# Main.net
KiCad netlist of a schematic drawn in EAGLE
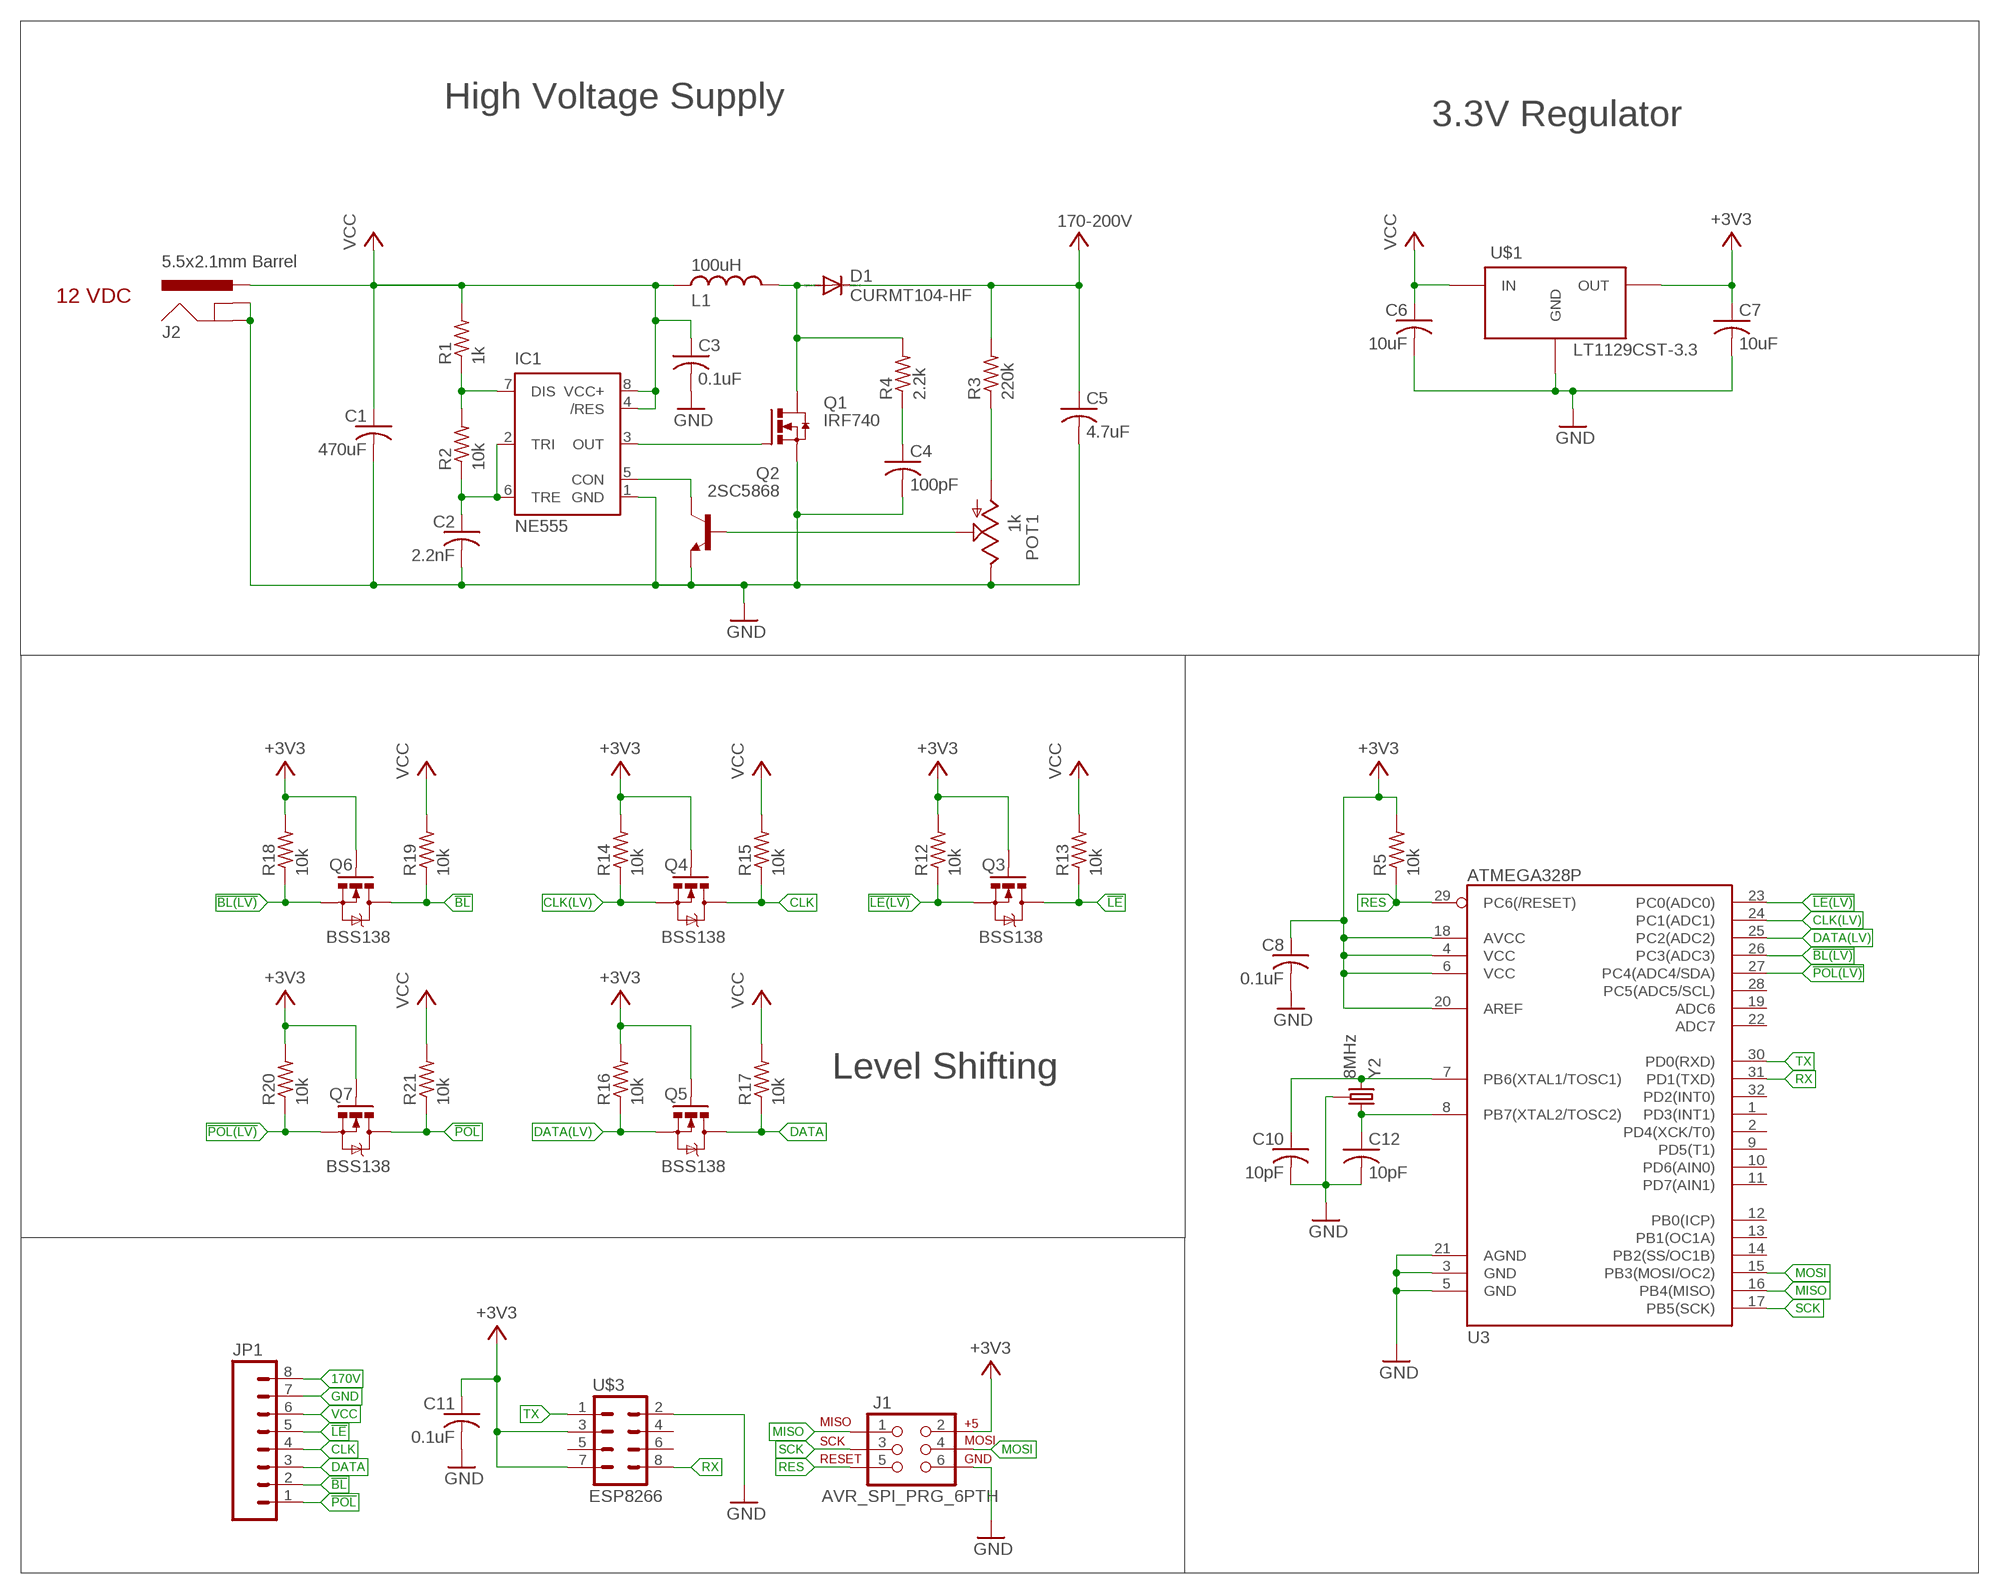
[diagram p0: schematic, sheet 1]

(export (version "E")
  (design (tool "Eeschema 10.0.6"))
  (components
    (comp (ref "C1")
      (value "470uF")
      (footprint "eagle-import:C0603")
      (libsource (lib "eagle-import") (part "C-USC0603"))
    )
    (comp (ref "C2")
      (value "2.2nF")
      (footprint "eagle-import:C0603")
      (libsource (lib "eagle-import") (part "C-USC0603"))
    )
    (comp (ref "C3")
      (value "0.1uF")
      (footprint "eagle-import:C0603")
      (libsource (lib "eagle-import") (part "C-USC0603"))
    )
    (comp (ref "C4")
      (value "100pF")
      (footprint "eagle-import:C0603")
      (libsource (lib "eagle-import") (part "C-USC0603"))
    )
    (comp (ref "C5")
      (value "4.7uF")
      (footprint "eagle-import:C0603")
      (libsource (lib "eagle-import") (part "C-USC0603"))
    )
    (comp (ref "C6")
      (value "10uF")
      (footprint "eagle-import:C0603")
      (libsource (lib "eagle-import") (part "C-USC0603"))
    )
    (comp (ref "C7")
      (value "10uF")
      (footprint "eagle-import:C0603")
      (libsource (lib "eagle-import") (part "C-USC0603"))
    )
    (comp (ref "C8")
      (value "0.1uF")
      (footprint "eagle-import:C0603")
      (libsource (lib "eagle-import") (part "C-USC0603"))
    )
    (comp (ref "C10")
      (value "10pF")
      (footprint "eagle-import:C0603")
      (libsource (lib "eagle-import") (part "C-USC0603"))
    )
    (comp (ref "C11")
      (value "0.1uF")
      (footprint "eagle-import:C0603")
      (libsource (lib "eagle-import") (part "C-USC0603"))
    )
    (comp (ref "C12")
      (value "10pF")
      (footprint "eagle-import:C0603")
      (libsource (lib "eagle-import") (part "C-USC0603"))
    )
    (comp (ref "D1")
      (value "CURMT104-HF")
      (footprint "eagle-import:SOD-123_MINI-SMA")
      (libsource (lib "eagle-import") (part "CGRM400-G1"))
    )
    (comp (ref "IC1")
      (value "NE555")
      (footprint "eagle-import:SO08")
      (libsource (lib "eagle-import") (part "NE555D"))
    )
    (comp (ref "J1")
      (value "AVR_SPI_PRG_6PTH")
      (footprint "eagle-import:2X3")
      (libsource (lib "eagle-import") (part "AVR_SPI_PRG_6PTH"))
    )
    (comp (ref "J2")
      (value "5.5x2.1mm Barrel")
      (footprint "eagle-import:POWER_JACK_SMD")
      (libsource (lib "eagle-import") (part "POWER_JACKSMD"))
    )
    (comp (ref "JP1")
      (value "M08")
      (footprint "eagle-import:1X08_PIN1_NO_SILK")
      (libsource (lib "eagle-import") (part "M08"))
    )
    (comp (ref "L1")
      (value "100uH")
      (footprint "eagle-import:L2012C")
      (libsource (lib "eagle-import") (part "L-USL2012C"))
    )
    (comp (ref "POT1")
      (value "1k")
      (footprint "eagle-import:1X03")
      (libsource (lib "eagle-import") (part "TRIM_US-DIL3"))
    )
    (comp (ref "Q1")
      (value "IRF740")
      (footprint "eagle-import:D2PACK")
      (libsource (lib "eagle-import") (part "IRF3704S"))
    )
    (comp (ref "Q2")
      (value "2SC5868")
      (footprint "eagle-import:SOT23-BEC")
      (libsource (lib "eagle-import") (part "BC850SMD"))
    )
    (comp (ref "Q3")
      (value "BSS138")
      (footprint "eagle-import:SOT23")
      (libsource (lib "eagle-import") (part "MOSFET-NCHANNELBSS138"))
    )
    (comp (ref "Q4")
      (value "BSS138")
      (footprint "eagle-import:SOT23")
      (libsource (lib "eagle-import") (part "MOSFET-NCHANNELBSS138"))
    )
    (comp (ref "Q5")
      (value "BSS138")
      (footprint "eagle-import:SOT23")
      (libsource (lib "eagle-import") (part "MOSFET-NCHANNELBSS138"))
    )
    (comp (ref "Q6")
      (value "BSS138")
      (footprint "eagle-import:SOT23")
      (libsource (lib "eagle-import") (part "MOSFET-NCHANNELBSS138"))
    )
    (comp (ref "Q7")
      (value "BSS138")
      (footprint "eagle-import:SOT23")
      (libsource (lib "eagle-import") (part "MOSFET-NCHANNELBSS138"))
    )
    (comp (ref "R1")
      (value "1k")
      (footprint "eagle-import:R0603")
      (libsource (lib "eagle-import") (part "R-US_R0603"))
    )
    (comp (ref "R2")
      (value "10k")
      (footprint "eagle-import:R0603")
      (libsource (lib "eagle-import") (part "R-US_R0603"))
    )
    (comp (ref "R3")
      (value "220k")
      (footprint "eagle-import:R0603")
      (libsource (lib "eagle-import") (part "R-US_R0603"))
    )
    (comp (ref "R4")
      (value "2.2k")
      (footprint "eagle-import:R0603")
      (libsource (lib "eagle-import") (part "R-US_R0603"))
    )
    (comp (ref "R5")
      (value "10k")
      (footprint "eagle-import:R0603")
      (libsource (lib "eagle-import") (part "R-US_R0603"))
    )
    (comp (ref "R12")
      (value "10k")
      (footprint "eagle-import:R0603")
      (libsource (lib "eagle-import") (part "R-US_R0603"))
    )
    (comp (ref "R13")
      (value "10k")
      (footprint "eagle-import:R0603")
      (libsource (lib "eagle-import") (part "R-US_R0603"))
    )
    (comp (ref "R14")
      (value "10k")
      (footprint "eagle-import:R0603")
      (libsource (lib "eagle-import") (part "R-US_R0603"))
    )
    (comp (ref "R15")
      (value "10k")
      (footprint "eagle-import:R0603")
      (libsource (lib "eagle-import") (part "R-US_R0603"))
    )
    (comp (ref "R16")
      (value "10k")
      (footprint "eagle-import:R0603")
      (libsource (lib "eagle-import") (part "R-US_R0603"))
    )
    (comp (ref "R17")
      (value "10k")
      (footprint "eagle-import:R0603")
      (libsource (lib "eagle-import") (part "R-US_R0603"))
    )
    (comp (ref "R18")
      (value "10k")
      (footprint "eagle-import:R0603")
      (libsource (lib "eagle-import") (part "R-US_R0603"))
    )
    (comp (ref "R19")
      (value "10k")
      (footprint "eagle-import:R0603")
      (libsource (lib "eagle-import") (part "R-US_R0603"))
    )
    (comp (ref "R20")
      (value "10k")
      (footprint "eagle-import:R0603")
      (libsource (lib "eagle-import") (part "R-US_R0603"))
    )
    (comp (ref "R21")
      (value "10k")
      (footprint "eagle-import:R0603")
      (libsource (lib "eagle-import") (part "R-US_R0603"))
    )
    (comp (ref "U$1")
      (value "LT1129CST-3.3")
      (footprint "eagle-import:SOT-223")
      (libsource (lib "eagle-import") (part "LT1129CST-3.3"))
    )
    (comp (ref "U$3")
      (value "ESP8266")
      (footprint "eagle-import:2X4")
      (libsource (lib "eagle-import") (part "M04X2"))
    )
    (comp (ref "U3")
      (value "ATMEGA328P")
      (footprint "eagle-import:TQFP32-08")
      (libsource (lib "eagle-import") (part "ATMEGA328_SMT"))
    )
    (comp (ref "Y2")
      (value "8MHz")
      (footprint "eagle-import:CTS406")
      (libsource (lib "eagle-import") (part "CRYSTALCTS406"))
    )
  )
  (nets
    (net (code "1") (name "+3V3") (class "Default")
      (node (ref "C11") (pin "1") (pinfunction "1_1") (pintype "passive"))
      (node (ref "C7") (pin "1") (pinfunction "1_1") (pintype "passive"))
      (node (ref "C8") (pin "1") (pinfunction "1_1") (pintype "passive"))
      (node (ref "J1") (pin "2") (pinfunction "2_2") (pintype "passive"))
      (node (ref "Q3") (pin "1") (pinfunction "G_1") (pintype "passive"))
      (node (ref "Q4") (pin "1") (pinfunction "G_1") (pintype "passive"))
      (node (ref "Q5") (pin "1") (pinfunction "G_1") (pintype "passive"))
      (node (ref "Q6") (pin "1") (pinfunction "G_1") (pintype "passive"))
      (node (ref "Q7") (pin "1") (pinfunction "G_1") (pintype "passive"))
      (node (ref "R12") (pin "2") (pinfunction "2_2") (pintype "passive"))
      (node (ref "R14") (pin "2") (pinfunction "2_2") (pintype "passive"))
      (node (ref "R16") (pin "2") (pinfunction "2_2") (pintype "passive"))
      (node (ref "R18") (pin "2") (pinfunction "2_2") (pintype "passive"))
      (node (ref "R20") (pin "2") (pinfunction "2_2") (pintype "passive"))
      (node (ref "R5") (pin "2") (pinfunction "2_2") (pintype "passive"))
      (node (ref "U$1") (pin "VOUT") (pinfunction "OUT_VOUT") (pintype "power_in"))
      (node (ref "U$3") (pin "3") (pinfunction "3_3") (pintype "passive"))
      (node (ref "U$3") (pin "7") (pinfunction "7_7") (pintype "passive"))
      (node (ref "U3") (pin "18") (pinfunction "AVCC_18") (pintype "bidirectional"))
      (node (ref "U3") (pin "20") (pinfunction "AREF_20") (pintype "bidirectional"))
      (node (ref "U3") (pin "4") (pinfunction "VCC_4") (pintype "bidirectional"))
      (node (ref "U3") (pin "6") (pinfunction "VCC_6") (pintype "bidirectional"))
    )
    (net (code "2") (name "/~{BL(LV})") (class "Default")
      (node (ref "Q6") (pin "2") (pinfunction "S_2") (pintype "passive"))
      (node (ref "R18") (pin "1") (pinfunction "1_1") (pintype "passive"))
      (node (ref "U3") (pin "26") (pinfunction "PC3(ADC3)_26") (pintype "bidirectional"))
    )
    (net (code "3") (name "/~{BL}") (class "Default")
      (node (ref "JP1") (pin "2") (pinfunction "2_2") (pintype "passive"))
      (node (ref "Q6") (pin "3") (pinfunction "D_3") (pintype "passive"))
      (node (ref "R19") (pin "1") (pinfunction "1_1") (pintype "passive"))
    )
    (net (code "4") (name "/~{LE(LV})") (class "Default")
      (node (ref "Q3") (pin "2") (pinfunction "S_2") (pintype "passive"))
      (node (ref "R12") (pin "1") (pinfunction "1_1") (pintype "passive"))
      (node (ref "U3") (pin "23") (pinfunction "PC0(ADC0)_23") (pintype "bidirectional"))
    )
    (net (code "5") (name "/~{LE}") (class "Default")
      (node (ref "JP1") (pin "5") (pinfunction "5_5") (pintype "passive"))
      (node (ref "Q3") (pin "3") (pinfunction "D_3") (pintype "passive"))
      (node (ref "R13") (pin "1") (pinfunction "1_1") (pintype "passive"))
    )
    (net (code "6") (name "/~{POL(LV})") (class "Default")
      (node (ref "Q7") (pin "2") (pinfunction "S_2") (pintype "passive"))
      (node (ref "R20") (pin "1") (pinfunction "1_1") (pintype "passive"))
      (node (ref "U3") (pin "27") (pinfunction "PC4(ADC4/SDA)_27") (pintype "bidirectional"))
    )
    (net (code "7") (name "/~{POL}") (class "Default")
      (node (ref "JP1") (pin "1") (pinfunction "1_1") (pintype "passive"))
      (node (ref "Q7") (pin "3") (pinfunction "D_3") (pintype "passive"))
      (node (ref "R21") (pin "1") (pinfunction "1_1") (pintype "passive"))
    )
    (net (code "8") (name "170V") (class "Default")
      (node (ref "C5") (pin "1") (pinfunction "1_1") (pintype "passive"))
      (node (ref "D1") (pin "C") (pinfunction "C_C") (pintype "passive"))
      (node (ref "JP1") (pin "8") (pinfunction "8_8") (pintype "passive"))
      (node (ref "R3") (pin "2") (pinfunction "2_2") (pintype "passive"))
    )
    (net (code "9") (name "CLK") (class "Default")
      (node (ref "JP1") (pin "4") (pinfunction "4_4") (pintype "passive"))
      (node (ref "Q4") (pin "3") (pinfunction "D_3") (pintype "passive"))
      (node (ref "R15") (pin "1") (pinfunction "1_1") (pintype "passive"))
    )
    (net (code "10") (name "CLK(LV)") (class "Default")
      (node (ref "Q4") (pin "2") (pinfunction "S_2") (pintype "passive"))
      (node (ref "R14") (pin "1") (pinfunction "1_1") (pintype "passive"))
      (node (ref "U3") (pin "24") (pinfunction "PC1(ADC1)_24") (pintype "bidirectional"))
    )
    (net (code "11") (name "DATA") (class "Default")
      (node (ref "JP1") (pin "3") (pinfunction "3_3") (pintype "passive"))
      (node (ref "Q5") (pin "3") (pinfunction "D_3") (pintype "passive"))
      (node (ref "R17") (pin "1") (pinfunction "1_1") (pintype "passive"))
    )
    (net (code "12") (name "DATA(LV)") (class "Default")
      (node (ref "Q5") (pin "2") (pinfunction "S_2") (pintype "passive"))
      (node (ref "R16") (pin "1") (pinfunction "1_1") (pintype "passive"))
      (node (ref "U3") (pin "25") (pinfunction "PC2(ADC2)_25") (pintype "bidirectional"))
    )
    (net (code "13") (name "GND") (class "Default")
      (node (ref "C1") (pin "2") (pinfunction "2_2") (pintype "passive"))
      (node (ref "C10") (pin "2") (pinfunction "2_2") (pintype "passive"))
      (node (ref "C11") (pin "2") (pinfunction "2_2") (pintype "passive"))
      (node (ref "C12") (pin "2") (pinfunction "2_2") (pintype "passive"))
      (node (ref "C2") (pin "2") (pinfunction "2_2") (pintype "passive"))
      (node (ref "C3") (pin "2") (pinfunction "2_2") (pintype "passive"))
      (node (ref "C4") (pin "2") (pinfunction "2_2") (pintype "passive"))
      (node (ref "C5") (pin "2") (pinfunction "2_2") (pintype "passive"))
      (node (ref "C6") (pin "2") (pinfunction "2_2") (pintype "passive"))
      (node (ref "C7") (pin "2") (pinfunction "2_2") (pintype "passive"))
      (node (ref "C8") (pin "2") (pinfunction "2_2") (pintype "passive"))
      (node (ref "IC1") (pin "1") (pinfunction "GND_1") (pintype "power_in"))
      (node (ref "J1") (pin "6") (pinfunction "6_6") (pintype "passive"))
      (node (ref "J2") (pin "GND") (pinfunction "GNDBREAK_GND") (pintype "bidirectional"))
      (node (ref "J2") (pin "P$4") (pinfunction "GND_P$4") (pintype "bidirectional"))
      (node (ref "JP1") (pin "7") (pinfunction "7_7") (pintype "passive"))
      (node (ref "POT1") (pin "3") (pinfunction "E_3") (pintype "passive"))
      (node (ref "Q1") (pin "3") (pinfunction "S_3") (pintype "passive"))
      (node (ref "Q2") (pin "E") (pinfunction "E_E") (pintype "passive"))
      (node (ref "U$1") (pin "GND") (pinfunction "GND_GND") (pintype "power_in"))
      (node (ref "U$1") (pin "GND1") (pinfunction "GND_GND1") (pintype "power_in"))
      (node (ref "U$3") (pin "2") (pinfunction "2_2") (pintype "passive"))
      (node (ref "U3") (pin "21") (pinfunction "AGND_21") (pintype "bidirectional"))
      (node (ref "U3") (pin "3") (pinfunction "GND_3") (pintype "bidirectional"))
      (node (ref "U3") (pin "5") (pinfunction "GND_5") (pintype "bidirectional"))
      (node (ref "Y2") (pin "2") (pinfunction "GND_2") (pintype "passive"))
      (node (ref "Y2") (pin "4") (pinfunction "GND_4") (pintype "passive"))
    )
    (net (code "14") (name "MISO") (class "Default")
      (node (ref "J1") (pin "1") (pinfunction "1_1") (pintype "passive"))
      (node (ref "U3") (pin "16") (pinfunction "PB4(MISO)_16") (pintype "bidirectional"))
    )
    (net (code "15") (name "MOSI") (class "Default")
      (node (ref "J1") (pin "4") (pinfunction "4_4") (pintype "passive"))
      (node (ref "U3") (pin "15") (pinfunction "PB3(MOSI/OC2)_15") (pintype "bidirectional"))
    )
    (net (code "16") (name "Net-(C4-Pad1)") (class "Default")
      (node (ref "C4") (pin "1") (pinfunction "1_1") (pintype "passive"))
      (node (ref "R4") (pin "1") (pinfunction "1_1") (pintype "passive"))
    )
    (net (code "17") (name "Net-(IC1-CON)") (class "Default")
      (node (ref "IC1") (pin "5") (pinfunction "CON_5") (pintype "input"))
      (node (ref "Q2") (pin "C") (pinfunction "C_C") (pintype "passive"))
    )
    (net (code "18") (name "Net-(IC1-DIS)") (class "Default")
      (node (ref "IC1") (pin "7") (pinfunction "DIS_7") (pintype "input"))
      (node (ref "R1") (pin "1") (pinfunction "1_1") (pintype "passive"))
      (node (ref "R2") (pin "2") (pinfunction "2_2") (pintype "passive"))
    )
    (net (code "19") (name "Net-(IC1-OUT)") (class "Default")
      (node (ref "IC1") (pin "3") (pinfunction "OUT_3") (pintype "output"))
      (node (ref "Q1") (pin "1") (pinfunction "G_1") (pintype "passive"))
    )
    (net (code "20") (name "Net-(IC1-TRE)") (class "Default")
      (node (ref "C2") (pin "1") (pinfunction "1_1") (pintype "passive"))
      (node (ref "IC1") (pin "2") (pinfunction "TRI_2") (pintype "input"))
      (node (ref "IC1") (pin "6") (pinfunction "TRE_6") (pintype "input"))
      (node (ref "R2") (pin "1") (pinfunction "1_1") (pintype "passive"))
    )
    (net (code "21") (name "Net-(POT1-A)") (class "Default")
      (node (ref "POT1") (pin "1") (pinfunction "A_1") (pintype "passive"))
      (node (ref "R3") (pin "1") (pinfunction "1_1") (pintype "passive"))
    )
    (net (code "22") (name "Net-(POT1-S)") (class "Default")
      (node (ref "POT1") (pin "2") (pinfunction "S_2") (pintype "passive"))
      (node (ref "Q2") (pin "B") (pinfunction "B_B") (pintype "passive"))
    )
    (net (code "23") (name "Net-(Q1-D)") (class "Default")
      (node (ref "D1") (pin "A") (pinfunction "A_A") (pintype "passive"))
      (node (ref "L1") (pin "1") (pinfunction "1_1") (pintype "passive"))
      (node (ref "Q1") (pin "2") (pinfunction "D_2") (pintype "passive"))
      (node (ref "R4") (pin "2") (pinfunction "2_2") (pintype "passive"))
    )
    (net (code "24") (name "Net-(U3-PB6(XTAL1{slash}TOSC1))") (class "Default")
      (node (ref "C10") (pin "1") (pinfunction "1_1") (pintype "passive"))
      (node (ref "U3") (pin "7") (pinfunction "PB6(XTAL1/TOSC1)_7") (pintype "bidirectional"))
      (node (ref "Y2") (pin "3") (pinfunction "2_3") (pintype "passive"))
    )
    (net (code "25") (name "Net-(U3-PB7(XTAL2{slash}TOSC2))") (class "Default")
      (node (ref "C12") (pin "1") (pinfunction "1_1") (pintype "passive"))
      (node (ref "U3") (pin "8") (pinfunction "PB7(XTAL2/TOSC2)_8") (pintype "bidirectional"))
      (node (ref "Y2") (pin "1") (pinfunction "1_1") (pintype "passive"))
    )
    (net (code "26") (name "RES") (class "Default")
      (node (ref "J1") (pin "5") (pinfunction "5_5") (pintype "passive"))
      (node (ref "R5") (pin "1") (pinfunction "1_1") (pintype "passive"))
      (node (ref "U3") (pin "29") (pinfunction "PC6(/RESET)_29") (pintype "bidirectional"))
    )
    (net (code "27") (name "RX") (class "Default")
      (node (ref "U$3") (pin "8") (pinfunction "8_8") (pintype "passive"))
      (node (ref "U3") (pin "31") (pinfunction "PD1(TXD)_31") (pintype "bidirectional"))
    )
    (net (code "28") (name "SCK") (class "Default")
      (node (ref "J1") (pin "3") (pinfunction "3_3") (pintype "passive"))
      (node (ref "U3") (pin "17") (pinfunction "PB5(SCK)_17") (pintype "bidirectional"))
    )
    (net (code "29") (name "TX") (class "Default")
      (node (ref "U$3") (pin "1") (pinfunction "1_1") (pintype "passive"))
      (node (ref "U3") (pin "30") (pinfunction "PD0(RXD)_30") (pintype "bidirectional"))
    )
    (net (code "30") (name "VCC") (class "Default")
      (node (ref "C1") (pin "1") (pinfunction "1_1") (pintype "passive"))
      (node (ref "C3") (pin "1") (pinfunction "1_1") (pintype "passive"))
      (node (ref "C6") (pin "1") (pinfunction "1_1") (pintype "passive"))
      (node (ref "IC1") (pin "4") (pinfunction "/RES_4") (pintype "input"))
      (node (ref "IC1") (pin "8") (pinfunction "VCC+_8") (pintype "power_in"))
      (node (ref "J2") (pin "VIN0") (pinfunction "PWR_VIN0") (pintype "bidirectional"))
      (node (ref "JP1") (pin "6") (pinfunction "6_6") (pintype "passive"))
      (node (ref "L1") (pin "2") (pinfunction "2_2") (pintype "passive"))
      (node (ref "R1") (pin "2") (pinfunction "2_2") (pintype "passive"))
      (node (ref "R13") (pin "2") (pinfunction "2_2") (pintype "passive"))
      (node (ref "R15") (pin "2") (pinfunction "2_2") (pintype "passive"))
      (node (ref "R17") (pin "2") (pinfunction "2_2") (pintype "passive"))
      (node (ref "R19") (pin "2") (pinfunction "2_2") (pintype "passive"))
      (node (ref "R21") (pin "2") (pinfunction "2_2") (pintype "passive"))
      (node (ref "U$1") (pin "VIN") (pinfunction "IN_VIN") (pintype "power_in"))
    )
    (net (code "31") (name "unconnected-(U$3-Pad4)") (class "Default")
      (node (ref "U$3") (pin "4") (pinfunction "4_4") (pintype "passive"))
    )
    (net (code "32") (name "unconnected-(U$3-Pad5)") (class "Default")
      (node (ref "U$3") (pin "5") (pinfunction "5_5") (pintype "passive"))
    )
    (net (code "33") (name "unconnected-(U$3-Pad6)") (class "Default")
      (node (ref "U$3") (pin "6") (pinfunction "6_6") (pintype "passive"))
    )
    (net (code "34") (name "unconnected-(U3-ADC6-Pad19)") (class "Default")
      (node (ref "U3") (pin "19") (pinfunction "ADC6_19") (pintype "bidirectional"))
    )
    (net (code "35") (name "unconnected-(U3-ADC7-Pad22)") (class "Default")
      (node (ref "U3") (pin "22") (pinfunction "ADC7_22") (pintype "bidirectional"))
    )
    (net (code "36") (name "unconnected-(U3-PB0(ICP)-Pad12)") (class "Default")
      (node (ref "U3") (pin "12") (pinfunction "PB0(ICP)_12") (pintype "bidirectional"))
    )
    (net (code "37") (name "unconnected-(U3-PB1(OC1A)-Pad13)") (class "Default")
      (node (ref "U3") (pin "13") (pinfunction "PB1(OC1A)_13") (pintype "bidirectional"))
    )
    (net (code "38") (name "unconnected-(U3-PB2(SS{slash}OC1B)-Pad14)") (class "Default")
      (node (ref "U3") (pin "14") (pinfunction "PB2(SS/OC1B)_14") (pintype "bidirectional"))
    )
    (net (code "39") (name "unconnected-(U3-PC5(ADC5{slash}SCL)-Pad28)") (class "Default")
      (node (ref "U3") (pin "28") (pinfunction "PC5(ADC5/SCL)_28") (pintype "bidirectional"))
    )
    (net (code "40") (name "unconnected-(U3-PD2(INT0)-Pad32)") (class "Default")
      (node (ref "U3") (pin "32") (pinfunction "PD2(INT0)_32") (pintype "bidirectional"))
    )
    (net (code "41") (name "unconnected-(U3-PD3(INT1)-Pad1)") (class "Default")
      (node (ref "U3") (pin "1") (pinfunction "PD3(INT1)_1") (pintype "bidirectional"))
    )
    (net (code "42") (name "unconnected-(U3-PD4(XCK{slash}T0)-Pad2)") (class "Default")
      (node (ref "U3") (pin "2") (pinfunction "PD4(XCK/T0)_2") (pintype "bidirectional"))
    )
    (net (code "43") (name "unconnected-(U3-PD5(T1)-Pad9)") (class "Default")
      (node (ref "U3") (pin "9") (pinfunction "PD5(T1)_9") (pintype "bidirectional"))
    )
    (net (code "44") (name "unconnected-(U3-PD6(AIN0)-Pad10)") (class "Default")
      (node (ref "U3") (pin "10") (pinfunction "PD6(AIN0)_10") (pintype "bidirectional"))
    )
    (net (code "45") (name "unconnected-(U3-PD7(AIN1)-Pad11)") (class "Default")
      (node (ref "U3") (pin "11") (pinfunction "PD7(AIN1)_11") (pintype "bidirectional"))
    )
  )
)
